# OSSIEPSNew.net
KiCad netlist of a schematic drawn in EAGLE
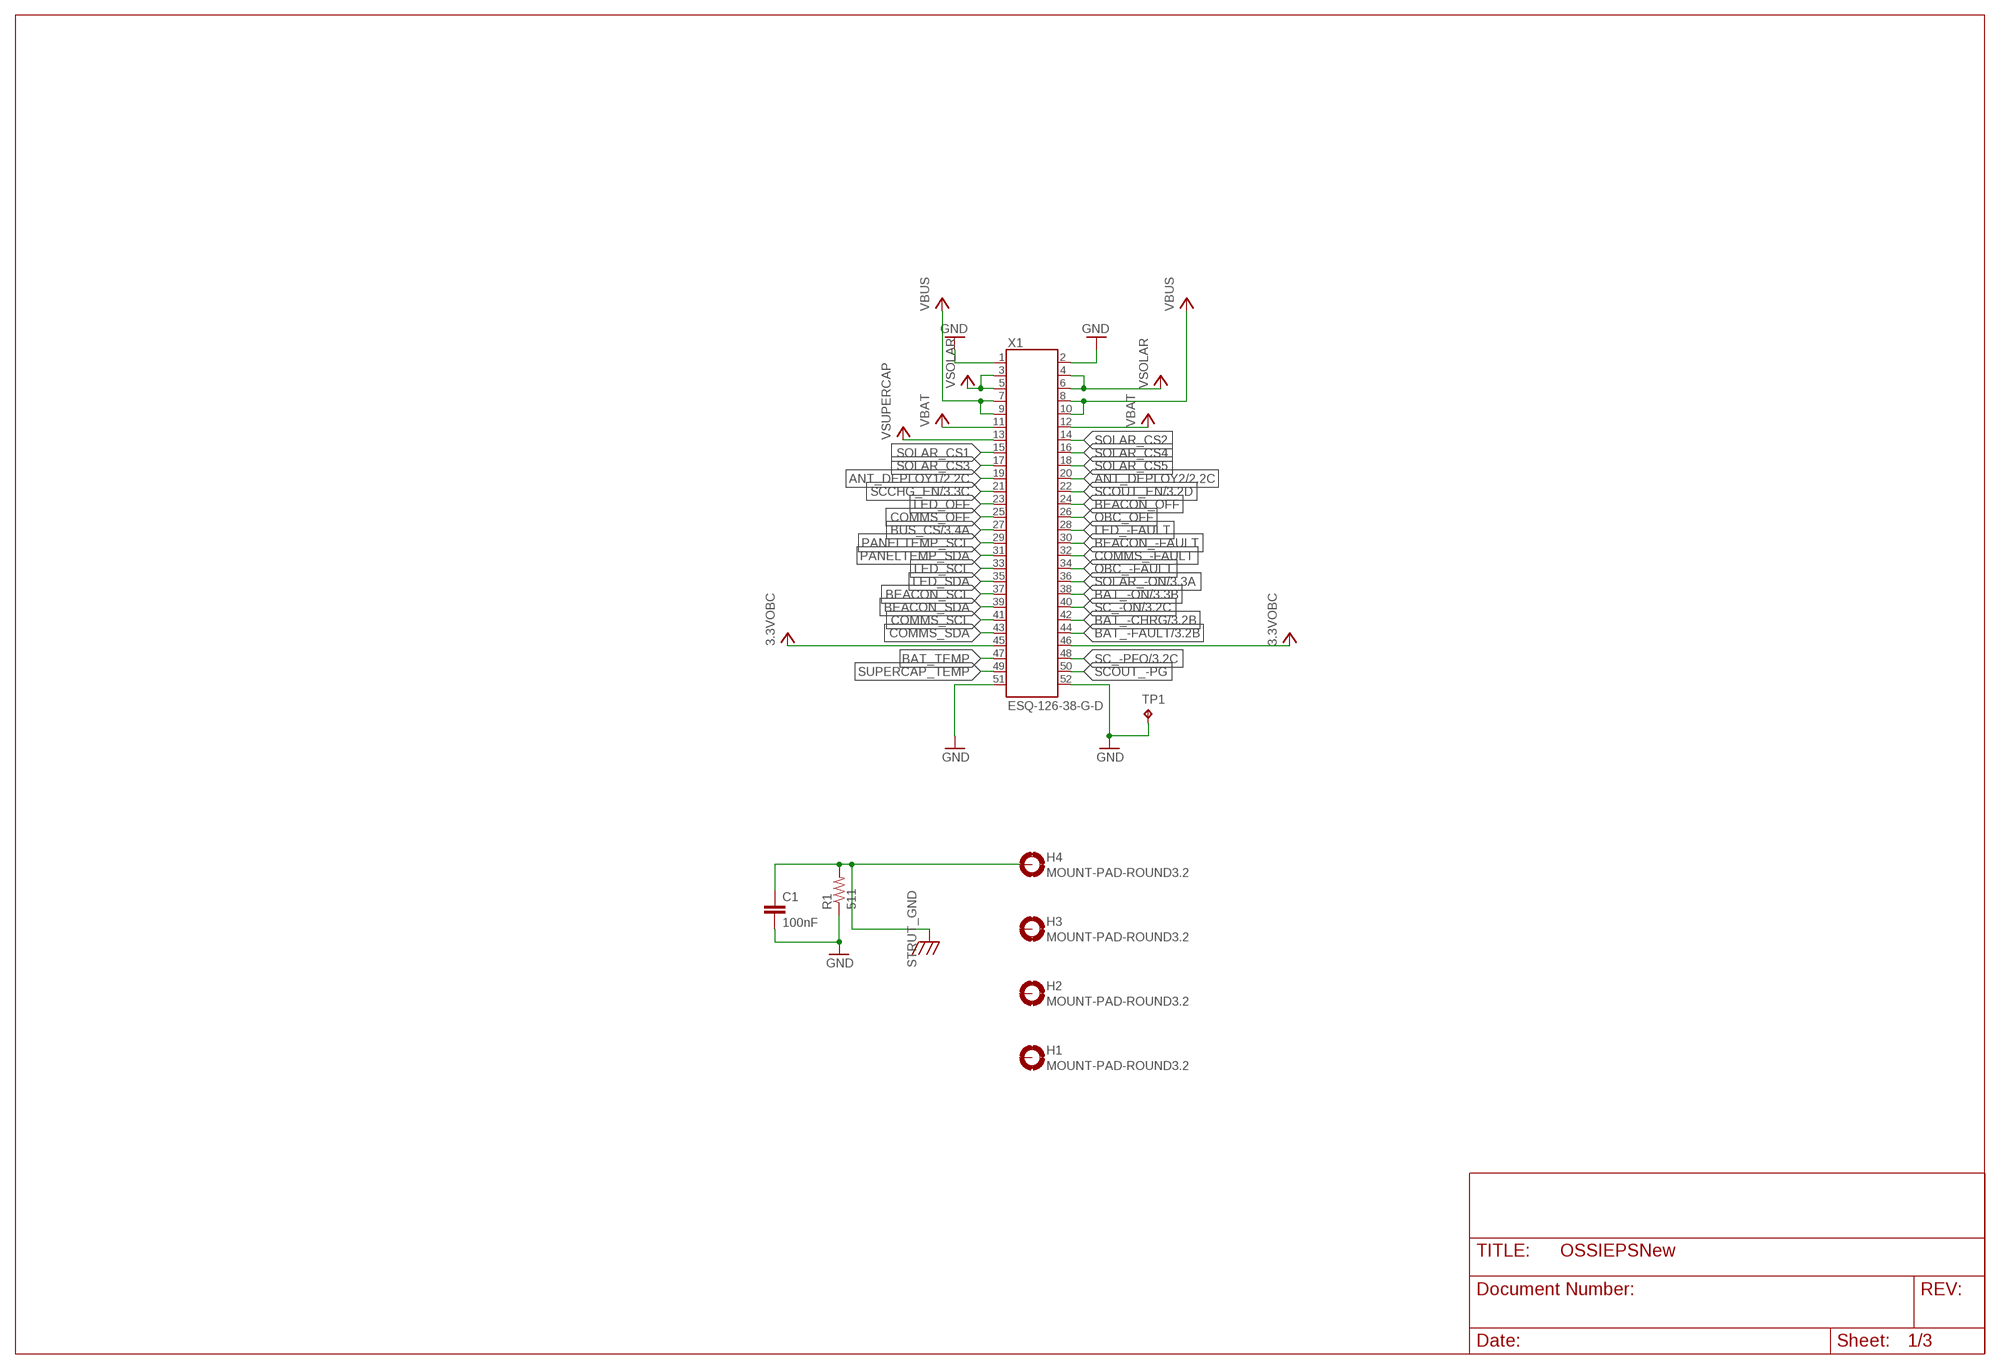
[diagram p0: schematic, sheet 1]
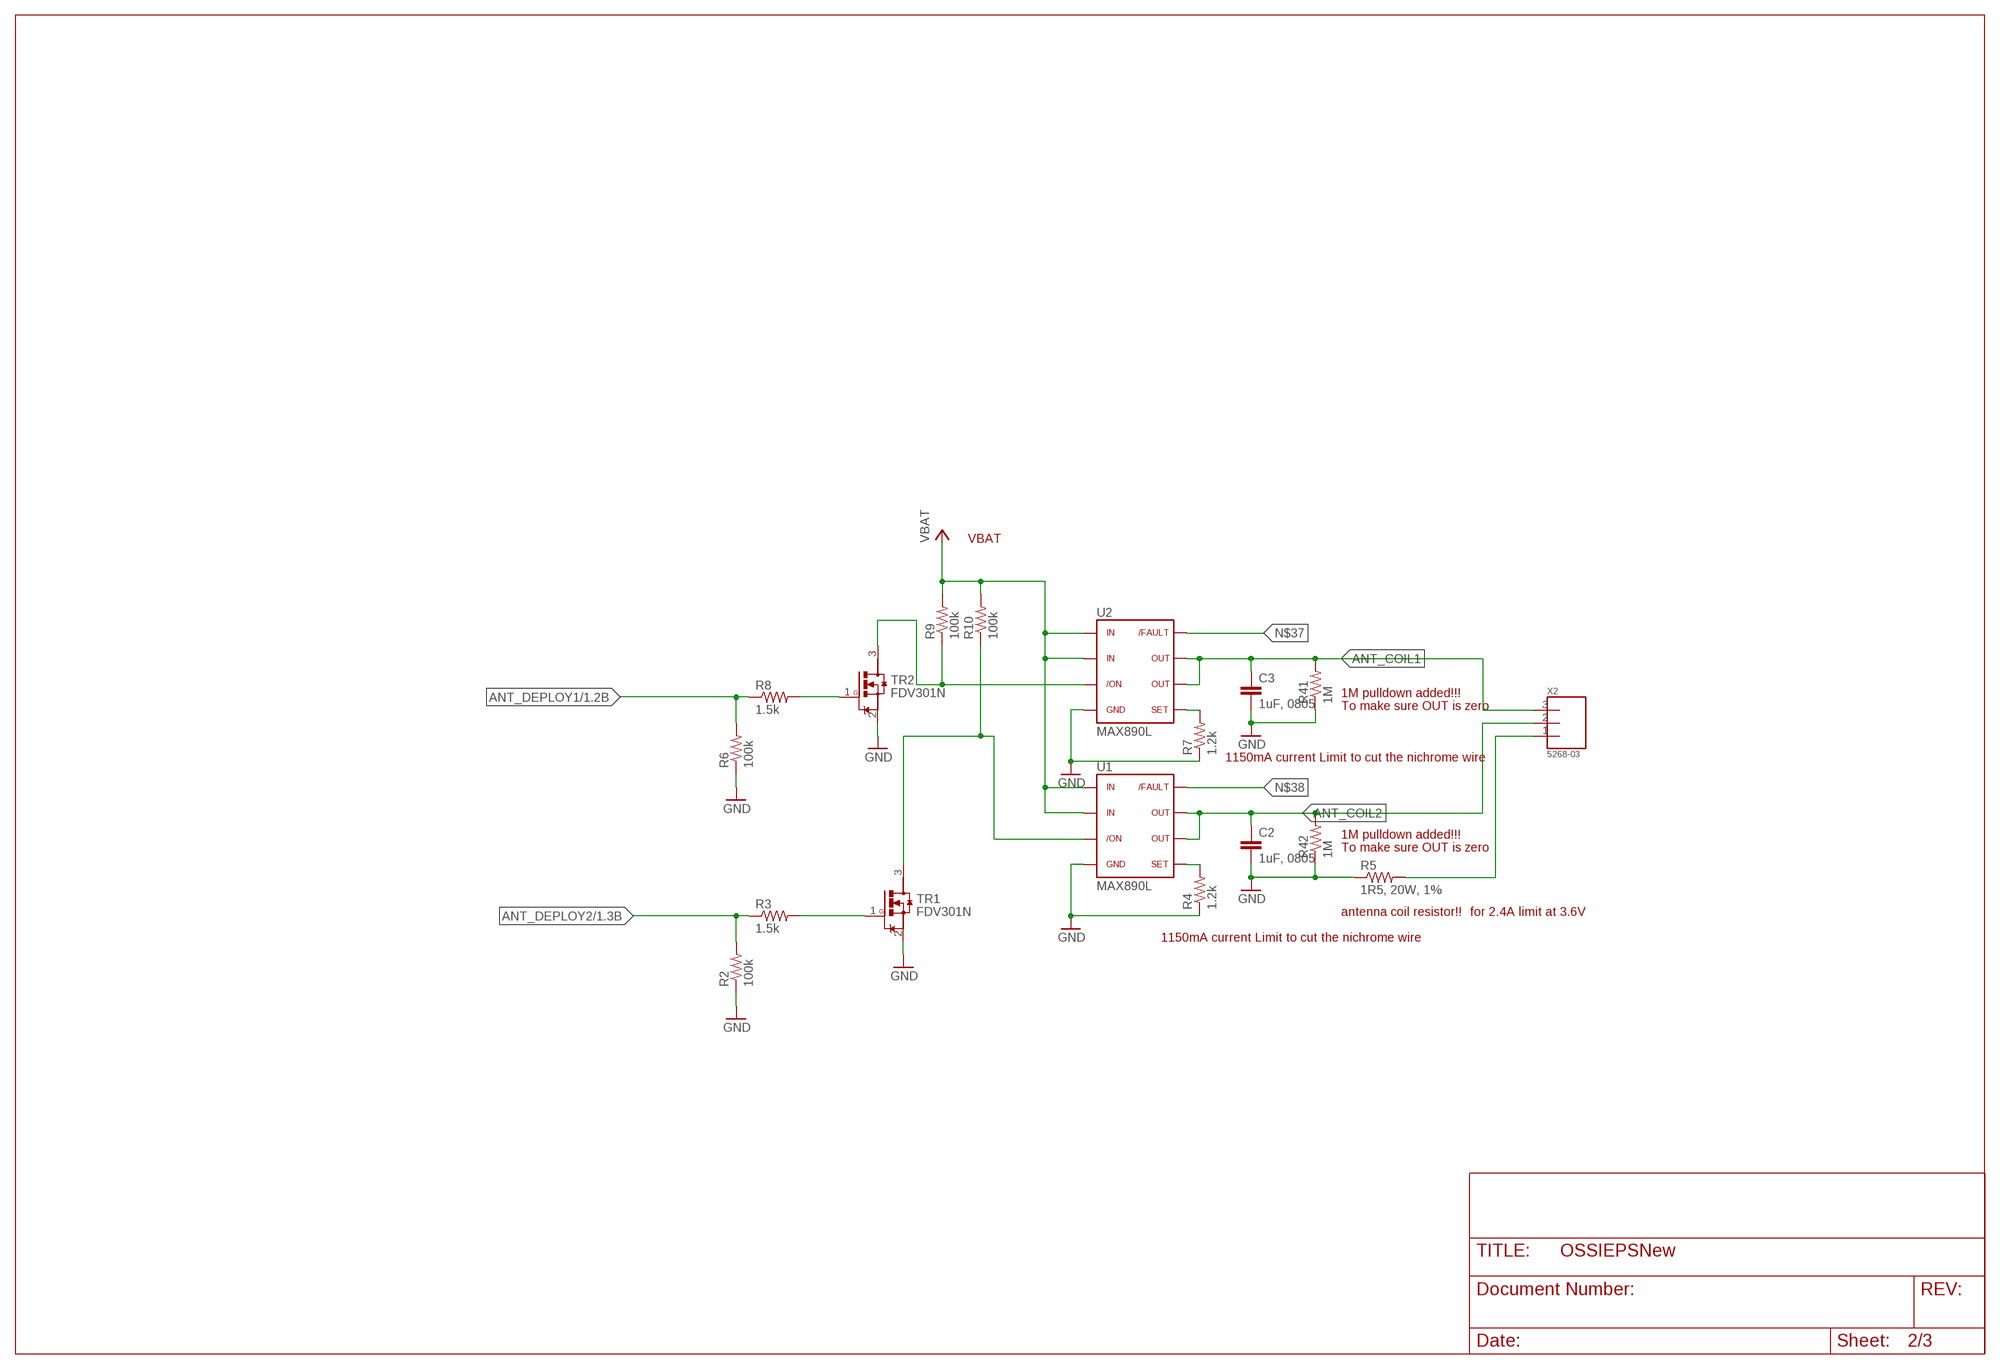
[diagram p1: schematic, sheet 2]
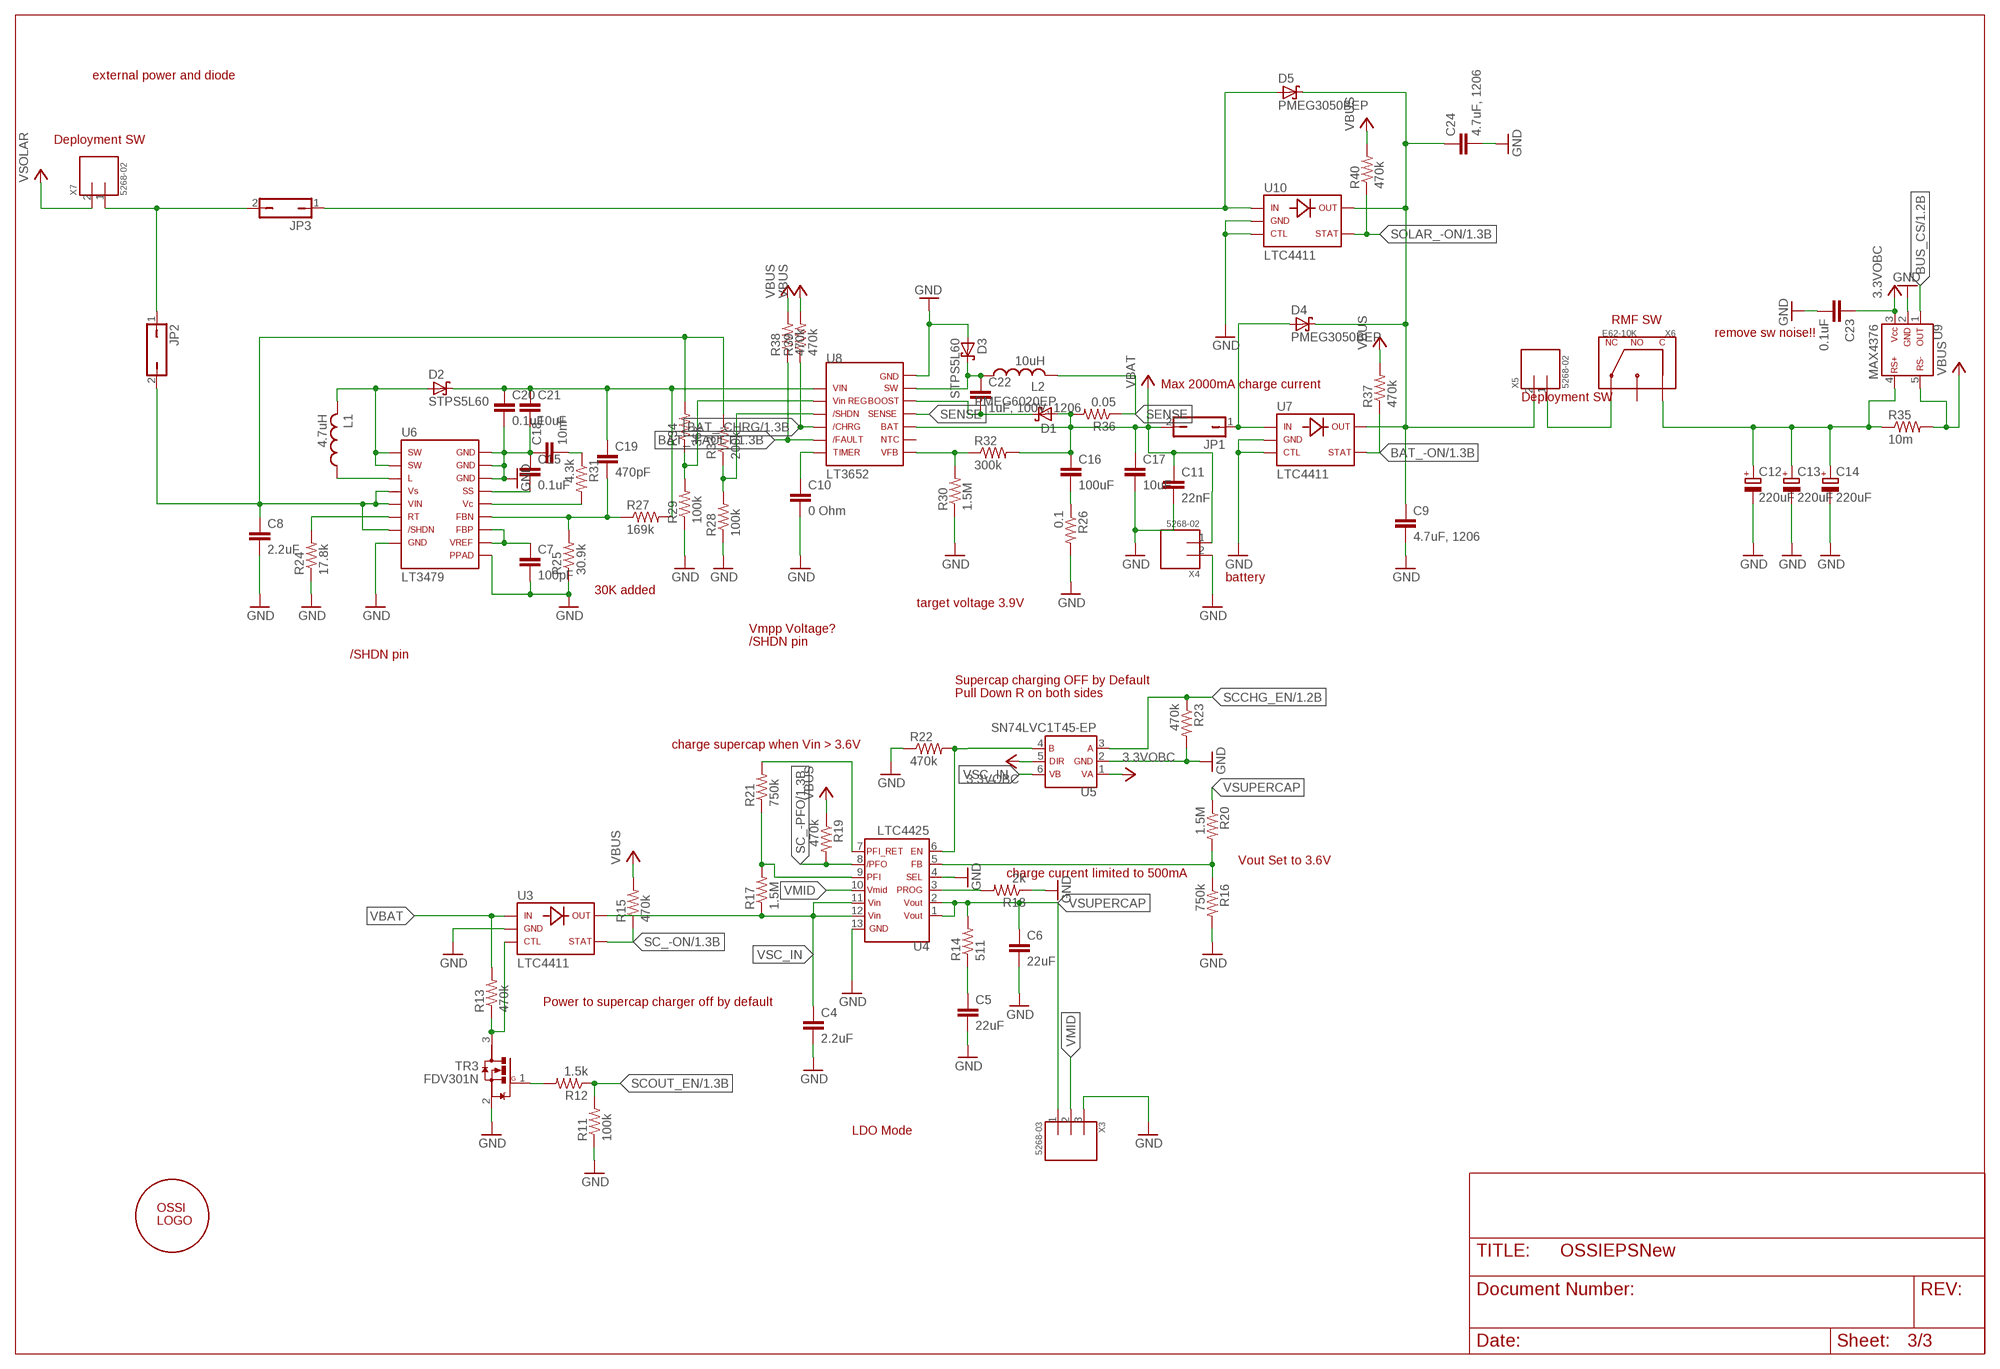
[diagram p2: schematic, sheet 3]

(export (version "E")
  (design (tool "Eeschema 10.0.6"))
  (components
    (comp (ref "C2")
      (value "1uF, 0805")
      (footprint "eagle-import:C0805(2012)")
      (libsource (lib "eagle-import") (part "C0805(2012)"))
    )
    (comp (ref "C3")
      (value "1uF, 0805")
      (footprint "eagle-import:C0805(2012)")
      (libsource (lib "eagle-import") (part "C0805(2012)"))
    )
    (comp (ref "R2")
      (value "100k")
      (footprint "eagle-import:R0603(1608)")
      (libsource (lib "eagle-import") (part "R0603(1608)"))
    )
    (comp (ref "R3")
      (value "1.5k")
      (footprint "eagle-import:R0603(1608)")
      (libsource (lib "eagle-import") (part "R0603(1608)"))
    )
    (comp (ref "R4")
      (value "1.2k")
      (footprint "eagle-import:R0603(1608)")
      (libsource (lib "eagle-import") (part "R0603(1608)"))
    )
    (comp (ref "R5")
      (value "1R5, 20W, 1%")
      (footprint "eagle-import:PWR263S-20")
      (libsource (lib "eagle-import") (part "RPWR263S"))
    )
    (comp (ref "R6")
      (value "100k")
      (footprint "eagle-import:R0603(1608)")
      (libsource (lib "eagle-import") (part "R0603(1608)"))
    )
    (comp (ref "R7")
      (value "1.2k")
      (footprint "eagle-import:R0603(1608)")
      (libsource (lib "eagle-import") (part "R0603(1608)"))
    )
    (comp (ref "R8")
      (value "1.5k")
      (footprint "eagle-import:R0603(1608)")
      (libsource (lib "eagle-import") (part "R0603(1608)"))
    )
    (comp (ref "R9")
      (value "100k")
      (footprint "eagle-import:R0603(1608)")
      (libsource (lib "eagle-import") (part "R0603(1608)"))
    )
    (comp (ref "R10")
      (value "100k")
      (footprint "eagle-import:R0603(1608)")
      (libsource (lib "eagle-import") (part "R0603(1608)"))
    )
    (comp (ref "R41")
      (value "1M")
      (footprint "eagle-import:R0603(1608)")
      (libsource (lib "eagle-import") (part "R0603(1608)"))
    )
    (comp (ref "R42")
      (value "1M")
      (footprint "eagle-import:R0603(1608)")
      (libsource (lib "eagle-import") (part "R0603(1608)"))
    )
    (comp (ref "TR1")
      (value "FDV301N")
      (footprint "eagle-import:SOT23")
      (libsource (lib "eagle-import") (part "FDV301N"))
    )
    (comp (ref "TR2")
      (value "FDV301N")
      (footprint "eagle-import:SOT23")
      (libsource (lib "eagle-import") (part "FDV301N"))
    )
    (comp (ref "U1")
      (value "MAX890L")
      (footprint "eagle-import:SO8")
      (libsource (lib "eagle-import") (part "MAX890L"))
    )
    (comp (ref "U2")
      (value "MAX890L")
      (footprint "eagle-import:SO8")
      (libsource (lib "eagle-import") (part "MAX890L"))
    )
    (comp (ref "X2")
      (value "5268-03")
      (footprint "eagle-import:5268-03")
      (libsource (lib "eagle-import") (part "5268-03"))
    )
    (comp (ref "C4")
      (value "2.2uF")
      (footprint "eagle-import:C1206-GCM31")
      (libsource (lib "eagle-import") (part "C1206(3216)-GCM31"))
    )
    (comp (ref "C5")
      (value "22uF")
      (footprint "eagle-import:C1210-GCM32")
      (libsource (lib "eagle-import") (part "C1210(3225)-GCM32"))
    )
    (comp (ref "C6")
      (value "22uF")
      (footprint "eagle-import:C1210-GCM32")
      (libsource (lib "eagle-import") (part "C1210(3225)-GCM32"))
    )
    (comp (ref "C7")
      (value "100pF")
      (footprint "eagle-import:C0603(1608)")
      (libsource (lib "eagle-import") (part "C0603(1608)"))
    )
    (comp (ref "C8")
      (value "2.2uF")
      (footprint "eagle-import:C1206-GCM31")
      (libsource (lib "eagle-import") (part "C1206(3216)-GCM31"))
    )
    (comp (ref "C9")
      (value "4.7uF, 1206")
      (footprint "eagle-import:C1206-GCM31")
      (libsource (lib "eagle-import") (part "C1206(3216)-GCM31"))
    )
    (comp (ref "C10")
      (value "0 Ohm")
      (footprint "eagle-import:C0603(1608)")
      (libsource (lib "eagle-import") (part "C0603(1608)"))
    )
    (comp (ref "C11")
      (value "22nF")
      (footprint "eagle-import:C0603(1608)")
      (libsource (lib "eagle-import") (part "C0603(1608)"))
    )
    (comp (ref "C12")
      (value "220uF")
      (footprint "eagle-import:C2917(7343)-Y")
      (libsource (lib "eagle-import") (part "C-TANTAL-Y"))
    )
    (comp (ref "C13")
      (value "220uF")
      (footprint "eagle-import:C2917(7343)-Y")
      (libsource (lib "eagle-import") (part "C-TANTAL-Y"))
    )
    (comp (ref "C14")
      (value "220uF")
      (footprint "eagle-import:C2917(7343)-Y")
      (libsource (lib "eagle-import") (part "C-TANTAL-Y"))
    )
    (comp (ref "C15")
      (value "0.1uF")
      (footprint "eagle-import:C0603(1608)")
      (libsource (lib "eagle-import") (part "C0603(1608)"))
    )
    (comp (ref "C16")
      (value "100uF")
      (footprint "eagle-import:C1210-TMK325")
      (libsource (lib "eagle-import") (part "C1210(3225)-TMK325"))
    )
    (comp (ref "C17")
      (value "10uF")
      (footprint "eagle-import:C1210-GCM32")
      (libsource (lib "eagle-import") (part "C1210(3225)-GCM32"))
    )
    (comp (ref "C18")
      (value "10nF")
      (footprint "eagle-import:C0603(1608)")
      (libsource (lib "eagle-import") (part "C0603(1608)"))
    )
    (comp (ref "C19")
      (value "470pF")
      (footprint "eagle-import:C0603(1608)")
      (libsource (lib "eagle-import") (part "C0603(1608)"))
    )
    (comp (ref "C20")
      (value "0.1uF")
      (footprint "eagle-import:C0603(1608)")
      (libsource (lib "eagle-import") (part "C0603(1608)"))
    )
    (comp (ref "C21")
      (value "10uF")
      (footprint "eagle-import:C1210-GCM32")
      (libsource (lib "eagle-import") (part "C1210(3225)-GCM32"))
    )
    (comp (ref "C22")
      (value "1uF, 100V, 1206")
      (footprint "eagle-import:C0805(2012)")
      (libsource (lib "eagle-import") (part "C0805(2012)"))
    )
    (comp (ref "C23")
      (value "0.1uF")
      (footprint "eagle-import:C0603(1608)")
      (libsource (lib "eagle-import") (part "C0603(1608)"))
    )
    (comp (ref "C24")
      (value "4.7uF, 1206")
      (footprint "eagle-import:C1206-GCM31")
      (libsource (lib "eagle-import") (part "C1206(3216)-GCM31"))
    )
    (comp (ref "D1")
      (value "PMEG6020EP")
      (footprint "eagle-import:PMEG6020EP")
      (libsource (lib "eagle-import") (part "PMEG6020EP"))
    )
    (comp (ref "D2")
      (value "STPS5L60")
      (footprint "eagle-import:STPS5L60")
      (libsource (lib "eagle-import") (part "STPS5L60"))
    )
    (comp (ref "D3")
      (value "STPS5L60")
      (footprint "eagle-import:STPS5L60")
      (libsource (lib "eagle-import") (part "STPS5L60"))
    )
    (comp (ref "D4")
      (value "PMEG3050BEP")
      (footprint "eagle-import:PMEG6020EP")
      (libsource (lib "eagle-import") (part "PMEG6020EP"))
    )
    (comp (ref "D5")
      (value "PMEG3050BEP")
      (footprint "eagle-import:PMEG6020EP")
      (libsource (lib "eagle-import") (part "PMEG6020EP"))
    )
    (comp (ref "JP1")
      (value "JP1Q")
      (footprint "eagle-import:JP1")
      (libsource (lib "eagle-import") (part "JP1Q"))
    )
    (comp (ref "JP2")
      (value "JP1Q")
      (footprint "eagle-import:JP1")
      (libsource (lib "eagle-import") (part "JP1Q"))
    )
    (comp (ref "JP3")
      (value "JP1Q")
      (footprint "eagle-import:JP1")
      (libsource (lib "eagle-import") (part "JP1Q"))
    )
    (comp (ref "L1")
      (value "4.7uH")
      (footprint "eagle-import:RLF7030")
      (libsource (lib "eagle-import") (part "LRLF7030"))
    )
    (comp (ref "L2")
      (value "10uH")
      (footprint "eagle-import:RLF12545")
      (libsource (lib "eagle-import") (part "LRLF12545"))
    )
    (comp (ref "R11")
      (value "100k")
      (footprint "eagle-import:R0603(1608)")
      (libsource (lib "eagle-import") (part "R0603(1608)"))
    )
    (comp (ref "R12")
      (value "1.5k")
      (footprint "eagle-import:R0603(1608)")
      (libsource (lib "eagle-import") (part "R0603(1608)"))
    )
    (comp (ref "R13")
      (value "470k")
      (footprint "eagle-import:R0603(1608)")
      (libsource (lib "eagle-import") (part "R0603(1608)"))
    )
    (comp (ref "R14")
      (value "511")
      (footprint "eagle-import:WSL1206")
      (libsource (lib "eagle-import") (part "RWSL1206"))
    )
    (comp (ref "R15")
      (value "470k")
      (footprint "eagle-import:R0603(1608)")
      (libsource (lib "eagle-import") (part "R0603(1608)"))
    )
    (comp (ref "R16")
      (value "750k")
      (footprint "eagle-import:R0603(1608)")
      (libsource (lib "eagle-import") (part "R0603(1608)"))
    )
    (comp (ref "R17")
      (value "1.5M")
      (footprint "eagle-import:R0603(1608)")
      (libsource (lib "eagle-import") (part "R0603(1608)"))
    )
    (comp (ref "R18")
      (value "2k")
      (footprint "eagle-import:R0603(1608)")
      (libsource (lib "eagle-import") (part "R0603(1608)"))
    )
    (comp (ref "R19")
      (value "470k")
      (footprint "eagle-import:R0603(1608)")
      (libsource (lib "eagle-import") (part "R0603(1608)"))
    )
    (comp (ref "R20")
      (value "1.5M")
      (footprint "eagle-import:R0603(1608)")
      (libsource (lib "eagle-import") (part "R0603(1608)"))
    )
    (comp (ref "R21")
      (value "750k")
      (footprint "eagle-import:R0603(1608)")
      (libsource (lib "eagle-import") (part "R0603(1608)"))
    )
    (comp (ref "R22")
      (value "470k")
      (footprint "eagle-import:R0603(1608)")
      (libsource (lib "eagle-import") (part "R0603(1608)"))
    )
    (comp (ref "R23")
      (value "470k")
      (footprint "eagle-import:R0603(1608)")
      (libsource (lib "eagle-import") (part "R0603(1608)"))
    )
    (comp (ref "R24")
      (value "17.8k")
      (footprint "eagle-import:R0603(1608)")
      (libsource (lib "eagle-import") (part "R0603(1608)"))
    )
    (comp (ref "R25")
      (value "30.9k")
      (footprint "eagle-import:R0603(1608)")
      (libsource (lib "eagle-import") (part "R0603(1608)"))
    )
    (comp (ref "R26")
      (value "0.1")
      (footprint "eagle-import:WSL1206")
      (libsource (lib "eagle-import") (part "RWSL1206"))
    )
    (comp (ref "R27")
      (value "169k")
      (footprint "eagle-import:R0603(1608)")
      (libsource (lib "eagle-import") (part "R0603(1608)"))
    )
    (comp (ref "R28")
      (value "100k")
      (footprint "eagle-import:R0603(1608)")
      (libsource (lib "eagle-import") (part "R0603(1608)"))
    )
    (comp (ref "R29")
      (value "100k")
      (footprint "eagle-import:R0603(1608)")
      (libsource (lib "eagle-import") (part "R0603(1608)"))
    )
    (comp (ref "R30")
      (value "1.5M")
      (footprint "eagle-import:R0603(1608)")
      (libsource (lib "eagle-import") (part "R0603(1608)"))
    )
    (comp (ref "R31")
      (value "4.3k")
      (footprint "eagle-import:R0603(1608)")
      (libsource (lib "eagle-import") (part "R0603(1608)"))
    )
    (comp (ref "R32")
      (value "300k")
      (footprint "eagle-import:R0603(1608)")
      (libsource (lib "eagle-import") (part "R0603(1608)"))
    )
    (comp (ref "R33")
      (value "200k")
      (footprint "eagle-import:R0603(1608)")
      (libsource (lib "eagle-import") (part "R0603(1608)"))
    )
    (comp (ref "R34")
      (value "36k")
      (footprint "eagle-import:R0603(1608)")
      (libsource (lib "eagle-import") (part "R0603(1608)"))
    )
    (comp (ref "R35")
      (value "10m")
      (footprint "eagle-import:WSL1206")
      (libsource (lib "eagle-import") (part "RWSL1206"))
    )
    (comp (ref "R36")
      (value "0.05")
      (footprint "eagle-import:WSL1206")
      (libsource (lib "eagle-import") (part "RWSL1206"))
    )
    (comp (ref "R37")
      (value "470k")
      (footprint "eagle-import:R0603(1608)")
      (libsource (lib "eagle-import") (part "R0603(1608)"))
    )
    (comp (ref "R38")
      (value "470k")
      (footprint "eagle-import:R0603(1608)")
      (libsource (lib "eagle-import") (part "R0603(1608)"))
    )
    (comp (ref "R39")
      (value "470k")
      (footprint "eagle-import:R0603(1608)")
      (libsource (lib "eagle-import") (part "R0603(1608)"))
    )
    (comp (ref "R40")
      (value "470k")
      (footprint "eagle-import:R0603(1608)")
      (libsource (lib "eagle-import") (part "R0603(1608)"))
    )
    (comp (ref "TR3")
      (value "FDV301N")
      (footprint "eagle-import:SOT23")
      (libsource (lib "eagle-import") (part "FDV301N"))
    )
    (comp (ref "U$1")
      (value "OSSILOGORECT")
      (footprint "eagle-import:OSSILOGORECT1005")
      (libsource (lib "eagle-import") (part "OSSILOGORECT"))
    )
    (comp (ref "U3")
      (value "LTC4411")
      (footprint "eagle-import:TSOT23-5")
      (libsource (lib "eagle-import") (part "LTC4411"))
    )
    (comp (ref "U4")
      (value "LTC4425")
      (footprint "eagle-import:MSE")
      (libsource (lib "eagle-import") (part "LTC4425"))
    )
    (comp (ref "U5")
      (value "SN74LVC1T45-EP")
      (footprint "eagle-import:SOT-6DCK")
      (libsource (lib "eagle-import") (part "SN74LVC1T45-EP"))
    )
    (comp (ref "U6")
      (value "LT3479")
      (footprint "eagle-import:TSSOP16-FE")
      (libsource (lib "eagle-import") (part "LT3479"))
    )
    (comp (ref "U7")
      (value "LTC4411")
      (footprint "eagle-import:TSOT23-5")
      (libsource (lib "eagle-import") (part "LTC4411"))
    )
    (comp (ref "U8")
      (value "LT3652")
      (footprint "eagle-import:MSE")
      (libsource (lib "eagle-import") (part "LT3652"))
    )
    (comp (ref "U9")
      (value "MAX4376")
      (footprint "eagle-import:SOT23-5DBV")
      (libsource (lib "eagle-import") (part "MAX4376"))
    )
    (comp (ref "U10")
      (value "LTC4411")
      (footprint "eagle-import:TSOT23-5")
      (libsource (lib "eagle-import") (part "LTC4411"))
    )
    (comp (ref "X3")
      (value "5268-03")
      (footprint "eagle-import:5268-03")
      (libsource (lib "eagle-import") (part "5268-03"))
    )
    (comp (ref "X4")
      (value "5268-02")
      (footprint "eagle-import:5628-02")
      (libsource (lib "eagle-import") (part "5268-02"))
    )
    (comp (ref "X5")
      (value "5268-02")
      (footprint "eagle-import:5628-02")
      (libsource (lib "eagle-import") (part "5268-02"))
    )
    (comp (ref "X6")
      (value "E62-10K")
      (footprint "eagle-import:E62-10K")
      (libsource (lib "eagle-import") (part "E62-10K"))
    )
    (comp (ref "X7")
      (value "5268-02")
      (footprint "eagle-import:5628-02")
      (libsource (lib "eagle-import") (part "5268-02"))
    )
    (comp (ref "C1")
      (value "100nF")
      (footprint "eagle-import:C0805(2012)")
      (libsource (lib "eagle-import") (part "C0805(2012)"))
    )
    (comp (ref "H1")
      (value "MOUNT-PAD-ROUND3.2")
      (footprint "eagle-import:3.2-PAD-ROUND")
      (libsource (lib "eagle-import") (part "MOUNT-PAD-ROUND3.2"))
    )
    (comp (ref "H2")
      (value "MOUNT-PAD-ROUND3.2")
      (footprint "eagle-import:3.2-PAD-ROUND")
      (libsource (lib "eagle-import") (part "MOUNT-PAD-ROUND3.2"))
    )
    (comp (ref "H3")
      (value "MOUNT-PAD-ROUND3.2")
      (footprint "eagle-import:3.2-PAD-ROUND")
      (libsource (lib "eagle-import") (part "MOUNT-PAD-ROUND3.2"))
    )
    (comp (ref "H4")
      (value "MOUNT-PAD-ROUND3.2")
      (footprint "eagle-import:3.2-PAD-ROUND")
      (libsource (lib "eagle-import") (part "MOUNT-PAD-ROUND3.2"))
    )
    (comp (ref "R1")
      (value "511")
      (footprint "eagle-import:WSL1206")
      (libsource (lib "eagle-import") (part "RWSL1206"))
    )
    (comp (ref "TP1")
      (value "TP")
      (footprint "eagle-import:TP-13")
      (libsource (lib "eagle-import") (part "TP"))
    )
    (comp (ref "X1")
      (value "ESQ-126-38-G-D")
      (footprint "eagle-import:ESQ-126-XX-X-D")
      (libsource (lib "eagle-import") (part "ESQ-126-38-G-D"))
    )
  )
  (nets
    (net (code "1") (name "3.3VOBC") (class "Default")
      (node (ref "C23") (pin "1") (pinfunction "1_1") (pintype "passive"))
      (node (ref "U5") (pin "1") (pinfunction "P$1_1") (pintype "bidirectional"))
      (node (ref "U5") (pin "5") (pinfunction "P$5_5") (pintype "bidirectional"))
      (node (ref "U9") (pin "3") (pinfunction "P$3_3") (pintype "power_in"))
      (node (ref "X1") (pin "45") (pinfunction "45_45") (pintype "bidirectional"))
      (node (ref "X1") (pin "46") (pinfunction "46_46") (pintype "bidirectional"))
    )
    (net (code "2") (name "ANT_COIL1") (class "Default")
      (node (ref "C3") (pin "1") (pinfunction "1_1") (pintype "passive"))
      (node (ref "R41") (pin "2") (pinfunction "2_2") (pintype "passive"))
      (node (ref "U2") (pin "6") (pinfunction "P$6_6") (pintype "output"))
      (node (ref "U2") (pin "7") (pinfunction "P$7_7") (pintype "output"))
      (node (ref "X2") (pin "3") (pinfunction "3_3") (pintype "bidirectional"))
    )
    (net (code "3") (name "ANT_COIL2") (class "Default")
      (node (ref "C2") (pin "1") (pinfunction "1_1") (pintype "passive"))
      (node (ref "R42") (pin "2") (pinfunction "2_2") (pintype "passive"))
      (node (ref "U1") (pin "6") (pinfunction "P$6_6") (pintype "output"))
      (node (ref "U1") (pin "7") (pinfunction "P$7_7") (pintype "output"))
      (node (ref "X2") (pin "2") (pinfunction "2_2") (pintype "bidirectional"))
    )
    (net (code "4") (name "ANT_DEPLOY1") (class "Default")
      (node (ref "R6") (pin "2") (pinfunction "2_2") (pintype "passive"))
      (node (ref "R8") (pin "1") (pinfunction "1_1") (pintype "passive"))
      (node (ref "X1") (pin "19") (pinfunction "19_19") (pintype "bidirectional"))
    )
    (net (code "5") (name "ANT_DEPLOY2") (class "Default")
      (node (ref "R2") (pin "2") (pinfunction "2_2") (pintype "passive"))
      (node (ref "R3") (pin "1") (pinfunction "1_1") (pintype "passive"))
      (node (ref "X1") (pin "20") (pinfunction "20_20") (pintype "bidirectional"))
    )
    (net (code "6") (name "BAT_-CHRG") (class "Default")
      (node (ref "R39") (pin "1") (pinfunction "1_1") (pintype "passive"))
      (node (ref "U8") (pin "4") (pinfunction "P$4_4") (pintype "output"))
      (node (ref "X1") (pin "42") (pinfunction "42_42") (pintype "bidirectional"))
    )
    (net (code "7") (name "BAT_-FAULT") (class "Default")
      (node (ref "R38") (pin "1") (pinfunction "1_1") (pintype "passive"))
      (node (ref "U8") (pin "5") (pinfunction "P$5_5") (pintype "output"))
      (node (ref "X1") (pin "44") (pinfunction "44_44") (pintype "bidirectional"))
    )
    (net (code "8") (name "BAT_-ON") (class "Default")
      (node (ref "R37") (pin "1") (pinfunction "1_1") (pintype "passive"))
      (node (ref "U7") (pin "P$4") (pinfunction "P$4_P$4") (pintype "output"))
      (node (ref "X1") (pin "38") (pinfunction "38_38") (pintype "bidirectional"))
    )
    (net (code "9") (name "BAT_TEMP") (class "Default")
      (node (ref "X1") (pin "47") (pinfunction "47_47") (pintype "bidirectional"))
    )
    (net (code "10") (name "BEACON_-FAULT") (class "Default")
      (node (ref "X1") (pin "30") (pinfunction "30_30") (pintype "bidirectional"))
    )
    (net (code "11") (name "BEACON_OFF") (class "Default")
      (node (ref "X1") (pin "24") (pinfunction "24_24") (pintype "bidirectional"))
    )
    (net (code "12") (name "BEACON_SCL") (class "Default")
      (node (ref "X1") (pin "37") (pinfunction "37_37") (pintype "bidirectional"))
    )
    (net (code "13") (name "BEACON_SDA") (class "Default")
      (node (ref "X1") (pin "39") (pinfunction "39_39") (pintype "bidirectional"))
    )
    (net (code "14") (name "BUS_CS") (class "Default")
      (node (ref "U9") (pin "1") (pinfunction "P$1_1") (pintype "output"))
      (node (ref "X1") (pin "27") (pinfunction "27_27") (pintype "bidirectional"))
    )
    (net (code "15") (name "COMMS_-FAULT") (class "Default")
      (node (ref "X1") (pin "32") (pinfunction "32_32") (pintype "bidirectional"))
    )
    (net (code "16") (name "COMMS_OFF") (class "Default")
      (node (ref "X1") (pin "25") (pinfunction "25_25") (pintype "bidirectional"))
    )
    (net (code "17") (name "COMMS_SCL") (class "Default")
      (node (ref "X1") (pin "41") (pinfunction "41_41") (pintype "bidirectional"))
    )
    (net (code "18") (name "COMMS_SDA") (class "Default")
      (node (ref "X1") (pin "43") (pinfunction "43_43") (pintype "bidirectional"))
    )
    (net (code "19") (name "GND") (class "Default")
      (node (ref "C1") (pin "2") (pinfunction "2_2") (pintype "passive"))
      (node (ref "C10") (pin "2") (pinfunction "2_2") (pintype "passive"))
      (node (ref "C11") (pin "2") (pinfunction "2_2") (pintype "passive"))
      (node (ref "C12") (pin "2") (pinfunction "-_2") (pintype "passive"))
      (node (ref "C13") (pin "2") (pinfunction "-_2") (pintype "passive"))
      (node (ref "C14") (pin "2") (pinfunction "-_2") (pintype "passive"))
      (node (ref "C15") (pin "1") (pinfunction "1_1") (pintype "passive"))
      (node (ref "C17") (pin "P$2") (pinfunction "2_P$2") (pintype "passive"))
      (node (ref "C18") (pin "1") (pinfunction "1_1") (pintype "passive"))
      (node (ref "C2") (pin "2") (pinfunction "2_2") (pintype "passive"))
      (node (ref "C20") (pin "2") (pinfunction "2_2") (pintype "passive"))
      (node (ref "C21") (pin "P$2") (pinfunction "2_P$2") (pintype "passive"))
      (node (ref "C23") (pin "2") (pinfunction "2_2") (pintype "passive"))
      (node (ref "C24") (pin "P$2") (pinfunction "2_P$2") (pintype "passive"))
      (node (ref "C3") (pin "2") (pinfunction "2_2") (pintype "passive"))
      (node (ref "C4") (pin "P$2") (pinfunction "2_P$2") (pintype "passive"))
      (node (ref "C5") (pin "P$2") (pinfunction "2_P$2") (pintype "passive"))
      (node (ref "C6") (pin "P$2") (pinfunction "2_P$2") (pintype "passive"))
      (node (ref "C7") (pin "2") (pinfunction "2_2") (pintype "passive"))
      (node (ref "C8") (pin "P$2") (pinfunction "2_P$2") (pintype "passive"))
      (node (ref "C9") (pin "P$2") (pinfunction "2_P$2") (pintype "passive"))
      (node (ref "D3") (pin "A") (pinfunction "A_A") (pintype "passive"))
      (node (ref "R1") (pin "P$1") (pinfunction "1_P$1") (pintype "passive"))
      (node (ref "R11") (pin "1") (pinfunction "1_1") (pintype "passive"))
      (node (ref "R16") (pin "2") (pinfunction "2_2") (pintype "passive"))
      (node (ref "R18") (pin "1") (pinfunction "1_1") (pintype "passive"))
      (node (ref "R2") (pin "1") (pinfunction "1_1") (pintype "passive"))
      (node (ref "R22") (pin "1") (pinfunction "1_1") (pintype "passive"))
      (node (ref "R23") (pin "2") (pinfunction "2_2") (pintype "passive"))
      (node (ref "R24") (pin "1") (pinfunction "1_1") (pintype "passive"))
      (node (ref "R25") (pin "1") (pinfunction "1_1") (pintype "passive"))
      (node (ref "R26") (pin "P$2") (pinfunction "2_P$2") (pintype "passive"))
      (node (ref "R28") (pin "1") (pinfunction "1_1") (pintype "passive"))
      (node (ref "R29") (pin "1") (pinfunction "1_1") (pintype "passive"))
      (node (ref "R30") (pin "1") (pinfunction "1_1") (pintype "passive"))
      (node (ref "R4") (pin "1") (pinfunction "1_1") (pintype "passive"))
      (node (ref "R41") (pin "1") (pinfunction "1_1") (pintype "passive"))
      (node (ref "R42") (pin "1") (pinfunction "1_1") (pintype "passive"))
      (node (ref "R5") (pin "P$1") (pinfunction "1_P$1") (pintype "passive"))
      (node (ref "R6") (pin "1") (pinfunction "1_1") (pintype "passive"))
      (node (ref "R7") (pin "1") (pinfunction "1_1") (pintype "passive"))
      (node (ref "TP1") (pin "TP") (pinfunction "TP_TP") (pintype "input"))
      (node (ref "TR1") (pin "2") (pinfunction "S_2") (pintype "bidirectional"))
      (node (ref "TR2") (pin "2") (pinfunction "S_2") (pintype "bidirectional"))
      (node (ref "TR3") (pin "2") (pinfunction "S_2") (pintype "bidirectional"))
      (node (ref "U1") (pin "4") (pinfunction "P$4_4") (pintype "power_in"))
      (node (ref "U10") (pin "P$2") (pinfunction "P$2_P$2") (pintype "power_in"))
      (node (ref "U10") (pin "P$3") (pinfunction "P$3_P$3") (pintype "input"))
      (node (ref "U2") (pin "4") (pinfunction "P$4_4") (pintype "power_in"))
      (node (ref "U3") (pin "P$2") (pinfunction "P$2_P$2") (pintype "power_in"))
      (node (ref "U4") (pin "13") (pinfunction "P$13_13") (pintype "power_in"))
      (node (ref "U4") (pin "4") (pinfunction "P$4_4") (pintype "input"))
      (node (ref "U5") (pin "2") (pinfunction "P$2_2") (pintype "bidirectional"))
      (node (ref "U6") (pin "14") (pinfunction "P$14_14") (pintype "power_in"))
      (node (ref "U6") (pin "15") (pinfunction "P$15_15") (pintype "power_in"))
      (node (ref "U6") (pin "16") (pinfunction "P$16_16") (pintype "power_in"))
      (node (ref "U6") (pin "8") (pinfunction "P$8_8") (pintype "power_in"))
      (node (ref "U6") (pin "PPAD") (pinfunction "P$17_PPAD") (pintype "power_in"))
      (node (ref "U7") (pin "P$2") (pinfunction "P$2_P$2") (pintype "power_in"))
      (node (ref "U7") (pin "P$3") (pinfunction "P$3_P$3") (pintype "input"))
      (node (ref "U8") (pin "13") (pinfunction "P$13_13") (pintype "bidirectional"))
      (node (ref "U9") (pin "2") (pinfunction "P$2_2") (pintype "power_in"))
      (node (ref "X1") (pin "1") (pinfunction "1_1") (pintype "bidirectional"))
      (node (ref "X1") (pin "2") (pinfunction "2_2") (pintype "bidirectional"))
      (node (ref "X1") (pin "51") (pinfunction "51_51") (pintype "bidirectional"))
      (node (ref "X1") (pin "52") (pinfunction "52_52") (pintype "bidirectional"))
      (node (ref "X3") (pin "3") (pinfunction "3_3") (pintype "bidirectional"))
      (node (ref "X4") (pin "2") (pinfunction "2_2") (pintype "bidirectional"))
    )
    (net (code "20") (name "LED_-FAULT") (class "Default")
      (node (ref "X1") (pin "28") (pinfunction "28_28") (pintype "bidirectional"))
    )
    (net (code "21") (name "LED_OFF") (class "Default")
      (node (ref "X1") (pin "23") (pinfunction "23_23") (pintype "bidirectional"))
    )
    (net (code "22") (name "LED_SCL") (class "Default")
      (node (ref "X1") (pin "33") (pinfunction "33_33") (pintype "bidirectional"))
    )
    (net (code "23") (name "LED_SDA") (class "Default")
      (node (ref "X1") (pin "35") (pinfunction "35_35") (pintype "bidirectional"))
    )
    (net (code "24") (name "N$37") (class "Default")
      (node (ref "U2") (pin "8") (pinfunction "P$8_8") (pintype "output"))
    )
    (net (code "25") (name "N$38") (class "Default")
      (node (ref "U1") (pin "8") (pinfunction "P$8_8") (pintype "output"))
    )
    (net (code "26") (name "Net-(C5-1)") (class "Default")
      (node (ref "C5") (pin "P$1") (pinfunction "1_P$1") (pintype "passive"))
      (node (ref "R14") (pin "P$1") (pinfunction "1_P$1") (pintype "passive"))
    )
    (net (code "27") (name "Net-(C8-1)") (class "Default")
      (node (ref "C8") (pin "P$1") (pinfunction "1_P$1") (pintype "passive"))
      (node (ref "JP2") (pin "2") (pinfunction "2_2") (pintype "passive"))
      (node (ref "R33") (pin "2") (pinfunction "2_2") (pintype "passive"))
      (node (ref "R34") (pin "2") (pinfunction "2_2") (pintype "passive"))
      (node (ref "U6") (pin "4") (pinfunction "P$4_4") (pintype "power_in"))
      (node (ref "U6") (pin "5") (pinfunction "P$5_5") (pintype "power_in"))
      (node (ref "U6") (pin "7") (pinfunction "P$7_7") (pintype "input"))
    )
    (net (code "28") (name "Net-(C12-+)") (class "Default")
      (node (ref "C12") (pin "1") (pinfunction "+_1") (pintype "passive"))
      (node (ref "C13") (pin "1") (pinfunction "+_1") (pintype "passive"))
      (node (ref "C14") (pin "1") (pinfunction "+_1") (pintype "passive"))
      (node (ref "R35") (pin "P$1") (pinfunction "1_P$1") (pintype "passive"))
      (node (ref "U9") (pin "4") (pinfunction "P$4_4") (pintype "input"))
      (node (ref "X6") (pin "C") (pinfunction "C_C") (pintype "bidirectional"))
    )
    (net (code "29") (name "Net-(C16-2)") (class "Default")
      (node (ref "C16") (pin "P$2") (pinfunction "2_P$2") (pintype "passive"))
      (node (ref "R26") (pin "P$1") (pinfunction "1_P$1") (pintype "passive"))
    )
    (net (code "30") (name "Net-(C18-Pad2)") (class "Default")
      (node (ref "C18") (pin "2") (pinfunction "2_2") (pintype "passive"))
      (node (ref "R31") (pin "1") (pinfunction "1_1") (pintype "passive"))
    )
    (net (code "31") (name "Net-(C21-1)") (class "Default")
      (node (ref "C19") (pin "1") (pinfunction "1_1") (pintype "passive"))
      (node (ref "C20") (pin "1") (pinfunction "1_1") (pintype "passive"))
      (node (ref "C21") (pin "P$1") (pinfunction "1_P$1") (pintype "passive"))
      (node (ref "D2") (pin "C") (pinfunction "C_C") (pintype "passive"))
      (node (ref "R27") (pin "2") (pinfunction "2_2") (pintype "passive"))
      (node (ref "U8") (pin "1") (pinfunction "P$1_1") (pintype "power_in"))
    )
    (net (code "32") (name "Net-(C24-1)") (class "Default")
      (node (ref "C24") (pin "P$1") (pinfunction "1_P$1") (pintype "passive"))
      (node (ref "C9") (pin "P$1") (pinfunction "1_P$1") (pintype "passive"))
      (node (ref "D4") (pin "C") (pinfunction "C_C") (pintype "passive"))
      (node (ref "D5") (pin "C") (pinfunction "C_C") (pintype "passive"))
      (node (ref "U10") (pin "P$5") (pinfunction "P$5_P$5") (pintype "power_in"))
      (node (ref "U7") (pin "P$5") (pinfunction "P$5_P$5") (pintype "power_in"))
      (node (ref "X5") (pin "2") (pinfunction "2_2") (pintype "bidirectional"))
    )
    (net (code "33") (name "Net-(D4-PadA)") (class "Default")
      (node (ref "D4") (pin "A") (pinfunction "A_A") (pintype "passive"))
      (node (ref "JP1") (pin "1") (pinfunction "1_1") (pintype "passive"))
      (node (ref "U7") (pin "P$1") (pinfunction "P$1_P$1") (pintype "input"))
    )
    (net (code "34") (name "Net-(D5-PadA)") (class "Default")
      (node (ref "D5") (pin "A") (pinfunction "A_A") (pintype "passive"))
      (node (ref "JP3") (pin "1") (pinfunction "1_1") (pintype "passive"))
      (node (ref "U10") (pin "P$1") (pinfunction "P$1_P$1") (pintype "input"))
    )
    (net (code "35") (name "Net-(JP2-Pad1)") (class "Default")
      (node (ref "JP2") (pin "1") (pinfunction "1_1") (pintype "passive"))
      (node (ref "JP3") (pin "2") (pinfunction "2_2") (pintype "passive"))
      (node (ref "X7") (pin "1") (pinfunction "1_1") (pintype "bidirectional"))
    )
    (net (code "36") (name "Net-(L1-1)") (class "Default")
      (node (ref "L1") (pin "P$1") (pinfunction "1_P$1") (pintype "passive"))
      (node (ref "U6") (pin "3") (pinfunction "P$3_3") (pintype "passive"))
    )
    (net (code "37") (name "Net-(L1-2)") (class "Default")
      (node (ref "D2") (pin "A") (pinfunction "A_A") (pintype "passive"))
      (node (ref "L1") (pin "P$2") (pinfunction "2_P$2") (pintype "passive"))
      (node (ref "U6") (pin "1") (pinfunction "P$1_1") (pintype "power_in"))
      (node (ref "U6") (pin "2") (pinfunction "P$2_2") (pintype "power_in"))
    )
    (net (code "38") (name "Net-(L2-1)") (class "Default")
      (node (ref "C22") (pin "1") (pinfunction "1_1") (pintype "passive"))
      (node (ref "D3") (pin "C") (pinfunction "C_C") (pintype "passive"))
      (node (ref "L2") (pin "P$1") (pinfunction "1_P$1") (pintype "passive"))
      (node (ref "U8") (pin "12") (pinfunction "P$12_12") (pintype "output"))
    )
    (net (code "39") (name "Net-(R5-2)") (class "Default")
      (node (ref "R5") (pin "P$2") (pinfunction "2_P$2") (pintype "passive"))
      (node (ref "X2") (pin "1") (pinfunction "1_1") (pintype "bidirectional"))
    )
    (net (code "40") (name "Net-(TR1-D)") (class "Default")
      (node (ref "R10") (pin "1") (pinfunction "1_1") (pintype "passive"))
      (node (ref "TR1") (pin "3") (pinfunction "D_3") (pintype "bidirectional"))
      (node (ref "U1") (pin "3") (pinfunction "P$3_3") (pintype "input"))
    )
    (net (code "41") (name "Net-(TR1-G)") (class "Default")
      (node (ref "R3") (pin "2") (pinfunction "2_2") (pintype "passive"))
      (node (ref "TR1") (pin "1") (pinfunction "G_1") (pintype "bidirectional"))
    )
    (net (code "42") (name "Net-(TR2-D)") (class "Default")
      (node (ref "R9") (pin "1") (pinfunction "1_1") (pintype "passive"))
      (node (ref "TR2") (pin "3") (pinfunction "D_3") (pintype "bidirectional"))
      (node (ref "U2") (pin "3") (pinfunction "P$3_3") (pintype "input"))
    )
    (net (code "43") (name "Net-(TR2-G)") (class "Default")
      (node (ref "R8") (pin "2") (pinfunction "2_2") (pintype "passive"))
      (node (ref "TR2") (pin "1") (pinfunction "G_1") (pintype "bidirectional"))
    )
    (net (code "44") (name "Net-(TR3-D)") (class "Default")
      (node (ref "R13") (pin "1") (pinfunction "1_1") (pintype "passive"))
      (node (ref "TR3") (pin "3") (pinfunction "D_3") (pintype "bidirectional"))
      (node (ref "U3") (pin "P$3") (pinfunction "P$3_P$3") (pintype "input"))
    )
    (net (code "45") (name "Net-(TR3-G)") (class "Default")
      (node (ref "R12") (pin "2") (pinfunction "2_2") (pintype "passive"))
      (node (ref "TR3") (pin "1") (pinfunction "G_1") (pintype "bidirectional"))
    )
    (net (code "46") (name "Net-(U1-P$5)") (class "Default")
      (node (ref "R4") (pin "2") (pinfunction "2_2") (pintype "passive"))
      (node (ref "U1") (pin "5") (pinfunction "P$5_5") (pintype "passive"))
    )
    (net (code "47") (name "Net-(U2-P$5)") (class "Default")
      (node (ref "R7") (pin "2") (pinfunction "2_2") (pintype "passive"))
      (node (ref "U2") (pin "5") (pinfunction "P$5_5") (pintype "passive"))
    )
    (net (code "48") (name "Net-(U4-P$3)") (class "Default")
      (node (ref "R18") (pin "2") (pinfunction "2_2") (pintype "passive"))
      (node (ref "U4") (pin "3") (pinfunction "P$3_3") (pintype "input"))
    )
    (net (code "49") (name "Net-(U4-P$5)") (class "Default")
      (node (ref "R16") (pin "1") (pinfunction "1_1") (pintype "passive"))
      (node (ref "R20") (pin "2") (pinfunction "2_2") (pintype "passive"))
      (node (ref "U4") (pin "5") (pinfunction "P$5_5") (pintype "input"))
    )
    (net (code "50") (name "Net-(U4-P$6)") (class "Default")
      (node (ref "R22") (pin "2") (pinfunction "2_2") (pintype "passive"))
      (node (ref "U4") (pin "6") (pinfunction "P$6_6") (pintype "input"))
      (node (ref "U5") (pin "4") (pinfunction "P$4_4") (pintype "bidirectional"))
    )
    (net (code "51") (name "Net-(U4-P$7)") (class "Default")
      (node (ref "R21") (pin "2") (pinfunction "2_2") (pintype "passive"))
      (node (ref "U4") (pin "7") (pinfunction "P$7_7") (pintype "input"))
    )
    (net (code "52") (name "Net-(U4-P$9)") (class "Default")
      (node (ref "R17") (pin "2") (pinfunction "2_2") (pintype "passive"))
      (node (ref "R21") (pin "1") (pinfunction "1_1") (pintype "passive"))
      (node (ref "U4") (pin "9") (pinfunction "P$9_9") (pintype "input"))
    )
    (net (code "53") (name "Net-(U6-P$6)") (class "Default")
      (node (ref "R24") (pin "2") (pinfunction "2_2") (pintype "passive"))
      (node (ref "U6") (pin "6") (pinfunction "P$6_6") (pintype "passive"))
    )
    (net (code "54") (name "Net-(U6-P$10)") (class "Default")
      (node (ref "C7") (pin "1") (pinfunction "1_1") (pintype "passive"))
      (node (ref "U6") (pin "10") (pinfunction "P$10_10") (pintype "input"))
      (node (ref "U6") (pin "9") (pinfunction "P$9_9") (pintype "output"))
    )
    (net (code "55") (name "Net-(U6-P$11)") (class "Default")
      (node (ref "C19") (pin "2") (pinfunction "2_2") (pintype "passive"))
      (node (ref "R25") (pin "2") (pinfunction "2_2") (pintype "passive"))
      (node (ref "R27") (pin "1") (pinfunction "1_1") (pintype "passive"))
      (node (ref "U6") (pin "11") (pinfunction "P$11_11") (pintype "input"))
    )
    (net (code "56") (name "Net-(U6-P$12)") (class "Default")
      (node (ref "R31") (pin "2") (pinfunction "2_2") (pintype "passive"))
      (node (ref "U6") (pin "12") (pinfunction "P$12_12") (pintype "input"))
    )
    (net (code "57") (name "Net-(U6-P$13)") (class "Default")
      (node (ref "C15") (pin "2") (pinfunction "2_2") (pintype "passive"))
      (node (ref "U6") (pin "13") (pinfunction "P$13_13") (pintype "input"))
    )
    (net (code "58") (name "Net-(U8-P$2)") (class "Default")
      (node (ref "R29") (pin "2") (pinfunction "2_2") (pintype "passive"))
      (node (ref "R34") (pin "1") (pinfunction "1_1") (pintype "passive"))
      (node (ref "U8") (pin "2") (pinfunction "P$2_2") (pintype "input"))
    )
    (net (code "59") (name "Net-(U8-P$3)") (class "Default")
      (node (ref "R28") (pin "2") (pinfunction "2_2") (pintype "passive"))
      (node (ref "R33") (pin "1") (pinfunction "1_1") (pintype "passive"))
      (node (ref "U8") (pin "3") (pinfunction "P$3_3") (pintype "input"))
    )
    (net (code "60") (name "Net-(U8-P$6)") (class "Default")
      (node (ref "C10") (pin "1") (pinfunction "1_1") (pintype "passive"))
      (node (ref "U8") (pin "6") (pinfunction "P$6_6") (pintype "input"))
    )
    (net (code "61") (name "Net-(U8-P$7)") (class "Default")
      (node (ref "R30") (pin "2") (pinfunction "2_2") (pintype "passive"))
      (node (ref "R32") (pin "1") (pinfunction "1_1") (pintype "passive"))
      (node (ref "U8") (pin "7") (pinfunction "P$7_7") (pintype "input"))
    )
    (net (code "62") (name "Net-(U8-P$11)") (class "Default")
      (node (ref "C22") (pin "2") (pinfunction "2_2") (pintype "passive"))
      (node (ref "D1") (pin "C") (pinfunction "C_C") (pintype "passive"))
      (node (ref "U8") (pin "11") (pinfunction "P$11_11") (pintype "input"))
    )
    (net (code "63") (name "Net-(X5-Pad1)") (class "Default")
      (node (ref "X5") (pin "1") (pinfunction "1_1") (pintype "bidirectional"))
      (node (ref "X6") (pin "NC") (pinfunction "NC_NC") (pintype "bidirectional"))
    )
    (net (code "64") (name "OBC_-FAULT") (class "Default")
      (node (ref "X1") (pin "34") (pinfunction "34_34") (pintype "bidirectional"))
    )
    (net (code "65") (name "OBC_OFF") (class "Default")
      (node (ref "X1") (pin "26") (pinfunction "26_26") (pintype "bidirectional"))
    )
    (net (code "66") (name "PANELTEMP_SCL") (class "Default")
      (node (ref "X1") (pin "29") (pinfunction "29_29") (pintype "bidirectional"))
    )
    (net (code "67") (name "PANELTEMP_SDA") (class "Default")
      (node (ref "X1") (pin "31") (pinfunction "31_31") (pintype "bidirectional"))
    )
    (net (code "68") (name "SCCHG_EN") (class "Default")
      (node (ref "R23") (pin "1") (pinfunction "1_1") (pintype "passive"))
      (node (ref "U5") (pin "3") (pinfunction "P$3_3") (pintype "bidirectional"))
      (node (ref "X1") (pin "21") (pinfunction "21_21") (pintype "bidirectional"))
    )
    (net (code "69") (name "SCOUT_-PG") (class "Default")
      (node (ref "X1") (pin "50") (pinfunction "50_50") (pintype "bidirectional"))
    )
    (net (code "70") (name "SCOUT_EN") (class "Default")
      (node (ref "R11") (pin "2") (pinfunction "2_2") (pintype "passive"))
      (node (ref "R12") (pin "1") (pinfunction "1_1") (pintype "passive"))
      (node (ref "X1") (pin "22") (pinfunction "22_22") (pintype "bidirectional"))
    )
    (net (code "71") (name "SC_-ON") (class "Default")
      (node (ref "R15") (pin "1") (pinfunction "1_1") (pintype "passive"))
      (node (ref "U3") (pin "P$4") (pinfunction "P$4_P$4") (pintype "output"))
      (node (ref "X1") (pin "40") (pinfunction "40_40") (pintype "bidirectional"))
    )
    (net (code "72") (name "SC_-PFO") (class "Default")
      (node (ref "R19") (pin "2") (pinfunction "2_2") (pintype "passive"))
      (node (ref "U4") (pin "8") (pinfunction "P$8_8") (pintype "output"))
      (node (ref "X1") (pin "48") (pinfunction "48_48") (pintype "bidirectional"))
    )
    (net (code "73") (name "SENSE") (class "Default")
      (node (ref "L2") (pin "P$2") (pinfunction "2_P$2") (pintype "passive"))
      (node (ref "R36") (pin "P$1") (pinfunction "1_P$1") (pintype "passive"))
      (node (ref "U8") (pin "10") (pinfunction "P$10_10") (pintype "input"))
    )
    (net (code "74") (name "SOLAR_-ON") (class "Default")
      (node (ref "R40") (pin "1") (pinfunction "1_1") (pintype "passive"))
      (node (ref "U10") (pin "P$4") (pinfunction "P$4_P$4") (pintype "output"))
      (node (ref "X1") (pin "36") (pinfunction "36_36") (pintype "bidirectional"))
    )
    (net (code "75") (name "SOLAR_CS1") (class "Default")
      (node (ref "X1") (pin "15") (pinfunction "15_15") (pintype "bidirectional"))
    )
    (net (code "76") (name "SOLAR_CS2") (class "Default")
      (node (ref "X1") (pin "14") (pinfunction "14_14") (pintype "bidirectional"))
    )
    (net (code "77") (name "SOLAR_CS3") (class "Default")
      (node (ref "X1") (pin "17") (pinfunction "17_17") (pintype "bidirectional"))
    )
    (net (code "78") (name "SOLAR_CS4") (class "Default")
      (node (ref "X1") (pin "16") (pinfunction "16_16") (pintype "bidirectional"))
    )
    (net (code "79") (name "SOLAR_CS5") (class "Default")
      (node (ref "X1") (pin "18") (pinfunction "18_18") (pintype "bidirectional"))
    )
    (net (code "80") (name "STRUT_GND") (class "Default")
      (node (ref "C1") (pin "1") (pinfunction "1_1") (pintype "passive"))
      (node (ref "H4") (pin "B3,2") (pinfunction "MOUNT_B3,2") (pintype "passive"))
      (node (ref "R1") (pin "P$2") (pinfunction "2_P$2") (pintype "passive"))
    )
    (net (code "81") (name "SUPERCAP_TEMP") (class "Default")
      (node (ref "X1") (pin "49") (pinfunction "49_49") (pintype "bidirectional"))
    )
    (net (code "82") (name "VBAT") (class "Default")
      (node (ref "C11") (pin "1") (pinfunction "1_1") (pintype "passive"))
      (node (ref "C16") (pin "P$1") (pinfunction "1_P$1") (pintype "passive"))
      (node (ref "C17") (pin "P$1") (pinfunction "1_P$1") (pintype "passive"))
      (node (ref "D1") (pin "A") (pinfunction "A_A") (pintype "passive"))
      (node (ref "JP1") (pin "2") (pinfunction "2_2") (pintype "passive"))
      (node (ref "R10") (pin "2") (pinfunction "2_2") (pintype "passive"))
      (node (ref "R13") (pin "2") (pinfunction "2_2") (pintype "passive"))
      (node (ref "R32") (pin "2") (pinfunction "2_2") (pintype "passive"))
      (node (ref "R36") (pin "P$2") (pinfunction "2_P$2") (pintype "passive"))
      (node (ref "R9") (pin "2") (pinfunction "2_2") (pintype "passive"))
      (node (ref "U1") (pin "1") (pinfunction "P$1_1") (pintype "input"))
      (node (ref "U1") (pin "2") (pinfunction "P$2_2") (pintype "input"))
      (node (ref "U2") (pin "1") (pinfunction "P$1_1") (pintype "input"))
      (node (ref "U2") (pin "2") (pinfunction "P$2_2") (pintype "input"))
      (node (ref "U3") (pin "P$1") (pinfunction "P$1_P$1") (pintype "input"))
      (node (ref "U8") (pin "9") (pinfunction "P$9_9") (pintype "input"))
      (node (ref "X1") (pin "11") (pinfunction "11_11") (pintype "bidirectional"))
      (node (ref "X1") (pin "12") (pinfunction "12_12") (pintype "bidirectional"))
      (node (ref "X4") (pin "1") (pinfunction "1_1") (pintype "bidirectional"))
    )
    (net (code "83") (name "VBUS") (class "Default")
      (node (ref "R15") (pin "2") (pinfunction "2_2") (pintype "passive"))
      (node (ref "R19") (pin "1") (pinfunction "1_1") (pintype "passive"))
      (node (ref "R35") (pin "P$2") (pinfunction "2_P$2") (pintype "passive"))
      (node (ref "R37") (pin "2") (pinfunction "2_2") (pintype "passive"))
      (node (ref "R38") (pin "2") (pinfunction "2_2") (pintype "passive"))
      (node (ref "R39") (pin "2") (pinfunction "2_2") (pintype "passive"))
      (node (ref "R40") (pin "2") (pinfunction "2_2") (pintype "passive"))
      (node (ref "U9") (pin "5") (pinfunction "P$5_5") (pintype "input"))
      (node (ref "X1") (pin "10") (pinfunction "10_10") (pintype "bidirectional"))
      (node (ref "X1") (pin "7") (pinfunction "7_7") (pintype "bidirectional"))
      (node (ref "X1") (pin "8") (pinfunction "8_8") (pintype "bidirectional"))
      (node (ref "X1") (pin "9") (pinfunction "9_9") (pintype "bidirectional"))
    )
    (net (code "84") (name "VMID") (class "Default")
      (node (ref "U4") (pin "10") (pinfunction "P$10_10") (pintype "power_in"))
      (node (ref "X3") (pin "2") (pinfunction "2_2") (pintype "bidirectional"))
    )
    (net (code "85") (name "VSC_IN") (class "Default")
      (node (ref "C4") (pin "P$1") (pinfunction "1_P$1") (pintype "passive"))
      (node (ref "R17") (pin "1") (pinfunction "1_1") (pintype "passive"))
      (node (ref "U3") (pin "P$5") (pinfunction "P$5_P$5") (pintype "power_in"))
      (node (ref "U4") (pin "11") (pinfunction "P$11_11") (pintype "power_in"))
      (node (ref "U4") (pin "12") (pinfunction "P$12_12") (pintype "power_in"))
      (node (ref "U5") (pin "6") (pinfunction "P$6_6") (pintype "bidirectional"))
    )
    (net (code "86") (name "VSOLAR") (class "Default")
      (node (ref "X1") (pin "3") (pinfunction "3_3") (pintype "bidirectional"))
      (node (ref "X1") (pin "4") (pinfunction "4_4") (pintype "bidirectional"))
      (node (ref "X1") (pin "5") (pinfunction "5_5") (pintype "bidirectional"))
      (node (ref "X1") (pin "6") (pinfunction "6_6") (pintype "bidirectional"))
      (node (ref "X7") (pin "2") (pinfunction "2_2") (pintype "bidirectional"))
    )
    (net (code "87") (name "VSUPERCAP") (class "Default")
      (node (ref "C6") (pin "P$1") (pinfunction "1_P$1") (pintype "passive"))
      (node (ref "R14") (pin "P$2") (pinfunction "2_P$2") (pintype "passive"))
      (node (ref "R20") (pin "1") (pinfunction "1_1") (pintype "passive"))
      (node (ref "U4") (pin "1") (pinfunction "P$1_1") (pintype "power_in"))
      (node (ref "U4") (pin "2") (pinfunction "P$2_2") (pintype "power_in"))
      (node (ref "X1") (pin "13") (pinfunction "13_13") (pintype "bidirectional"))
      (node (ref "X3") (pin "1") (pinfunction "1_1") (pintype "bidirectional"))
    )
    (net (code "88") (name "unconnected-(H1-MOUNT-PadB3,2)") (class "Default")
      (node (ref "H1") (pin "B3,2") (pinfunction "MOUNT_B3,2") (pintype "passive"))
    )
    (net (code "89") (name "unconnected-(H2-MOUNT-PadB3,2)") (class "Default")
      (node (ref "H2") (pin "B3,2") (pinfunction "MOUNT_B3,2") (pintype "passive"))
    )
    (net (code "90") (name "unconnected-(H3-MOUNT-PadB3,2)") (class "Default")
      (node (ref "H3") (pin "B3,2") (pinfunction "MOUNT_B3,2") (pintype "passive"))
    )
    (net (code "91") (name "unconnected-(U8-P$8-Pad8)") (class "Default")
      (node (ref "U8") (pin "8") (pinfunction "P$8_8") (pintype "input"))
    )
    (net (code "92") (name "unconnected-(X6-PadNO)") (class "Default")
      (node (ref "X6") (pin "NO") (pinfunction "NO_NO") (pintype "bidirectional"))
    )
  )
)
